# Faceball_2000_buffered_adapter_v1_0.net
KiCad netlist of a schematic drawn in Altium Designer
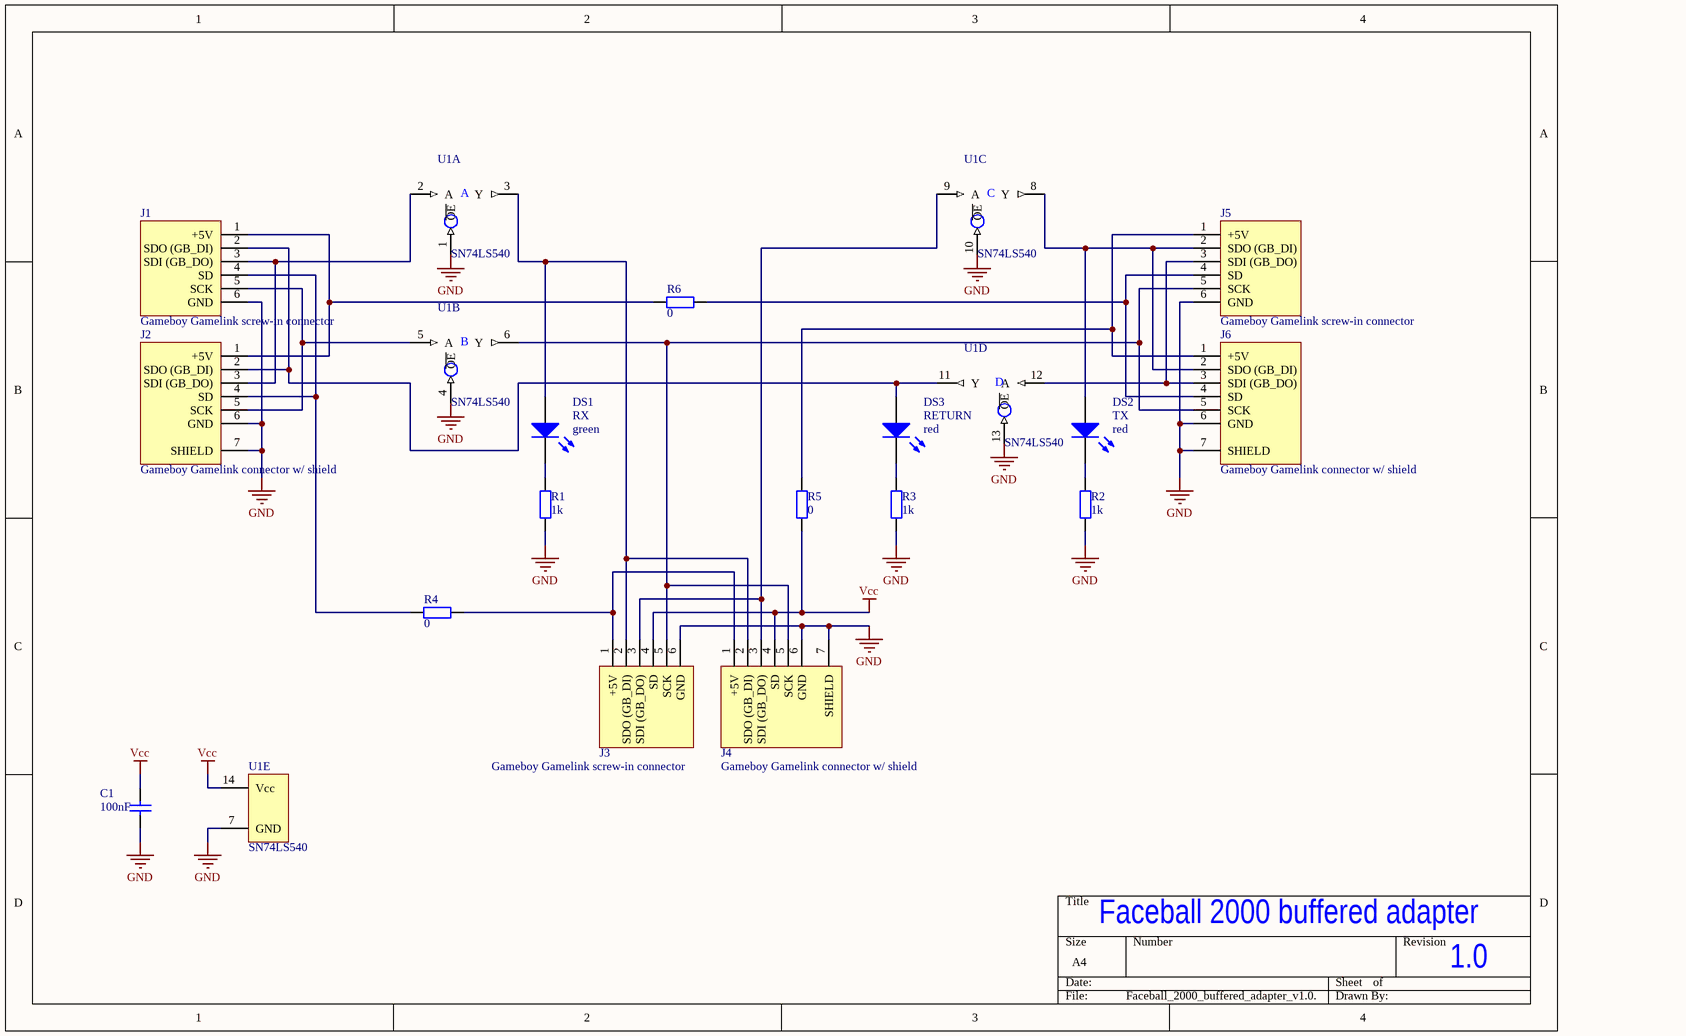
[diagram p0: Faceball_2000_buffered_adapter_v1.0.SchDoc]

(export (version "E")
  (design (tool "Eeschema 10.0.6"))
  (components
    (comp (ref "C1")
      (value "100nF")
      (footprint "CAPC1608N-0603")
      (description "Capacitor")
      (fields
        (field (name "MANUFACTURER") "Generic Components")
        (field (name "Comment") "Cap Unpol")
        (field (name "PUBLISHER") "Altium Limited")
      )
      (libsource (lib "alex_bahr") (part "Cap Unpol"))
    )
    (comp (ref "DS1")
      (value "LED")
      (footprint "CD2012-0805")
      (description "Typical LED red")
      (fields
        (field (name "MANUFACTURER") "Generic Components")
        (field (name "PURPOSE") "RX")
        (field (name "COLOR") "green")
        (field (name "PUBLISHER") "Altium Limited")
      )
      (libsource (lib "alex_bahr") (part "LED red"))
    )
    (comp (ref "DS2")
      (value "LED")
      (footprint "CD2012-0805")
      (description "Typical LED red")
      (fields
        (field (name "MANUFACTURER") "Generic Components")
        (field (name "PURPOSE") "TX")
        (field (name "COLOR") "red")
        (field (name "PUBLISHER") "Altium Limited")
      )
      (libsource (lib "alex_bahr") (part "LED red"))
    )
    (comp (ref "DS3")
      (value "LED")
      (footprint "CD2012-0805")
      (description "Typical LED red")
      (fields
        (field (name "MANUFACTURER") "Generic Components")
        (field (name "PURPOSE") "RETURN")
        (field (name "COLOR") "red")
        (field (name "PUBLISHER") "Altium Limited")
      )
      (libsource (lib "alex_bahr") (part "LED red"))
    )
    (comp (ref "J1")
      (value "Gameboy Gamelink screw-in connector")
      (footprint "Gameboy generic Gamelink connector")
      (description "Gameboy Gamelink connector")
      (libsource (lib "alex_bahr") (part "Gameboy Gamelink screw-in connector"))
    )
    (comp (ref "J2")
      (value "Gameboy Gamelink connector w/ shield")
      (footprint "Gameboy Advance Gamelink connector 2")
      (description "Gameboy Gamelink connector")
      (libsource (lib "") (part "Gameboy Gamelink connector w/ shield_1"))
    )
    (comp (ref "J3")
      (value "Gameboy Gamelink screw-in connector")
      (footprint "Gameboy generic Gamelink connector")
      (description "Gameboy Gamelink connector")
      (libsource (lib "") (part "Gameboy Gamelink screw-in connector_2"))
    )
    (comp (ref "J4")
      (value "Gameboy Gamelink connector w/ shield")
      (footprint "Gameboy Advance Gamelink connector 2")
      (description "Gameboy Gamelink connector")
      (libsource (lib "alex_bahr") (part "Gameboy Gamelink connector w/ shield"))
    )
    (comp (ref "J5")
      (value "Gameboy Gamelink screw-in connector")
      (footprint "Gameboy generic Gamelink connector")
      (description "Gameboy Gamelink connector")
      (libsource (lib "") (part "Gameboy Gamelink screw-in connector_1"))
    )
    (comp (ref "J6")
      (value "Gameboy Gamelink connector w/ shield")
      (footprint "Gameboy Advance Gamelink connector 2")
      (description "Gameboy Gamelink connector")
      (libsource (lib "") (part "Gameboy Gamelink connector w/ shield_2"))
    )
    (comp (ref "R1")
      (value "1k")
      (footprint "RESC1608N-0603")
      (description "Resistor")
      (fields (field (name "PUBLISHER") "Altium Limited"))
      (libsource (lib "") (part "Resistor_3"))
    )
    (comp (ref "R2")
      (value "1k")
      (footprint "RESC1608N-0603")
      (description "Resistor")
      (fields (field (name "PUBLISHER") "Altium Limited"))
      (libsource (lib "") (part "Resistor_3"))
    )
    (comp (ref "R3")
      (value "1k")
      (footprint "RESC1608N-0603")
      (description "Resistor")
      (fields (field (name "PUBLISHER") "Altium Limited"))
      (libsource (lib "") (part "Resistor_3"))
    )
    (comp (ref "R4")
      (value "0")
      (footprint "RESC1608N-0603")
      (description "Resistor")
      (fields (field (name "PUBLISHER") "Altium Limited"))
      (libsource (lib "") (part "Resistor_2"))
    )
    (comp (ref "R5")
      (value "0")
      (footprint "RESC1608N-0603")
      (description "Resistor")
      (fields (field (name "PUBLISHER") "Altium Limited"))
      (libsource (lib "alex_bahr") (part "Resistor"))
    )
    (comp (ref "R6")
      (value "0")
      (footprint "RESC1608N-0603")
      (description "Resistor")
      (fields (field (name "PUBLISHER") "Altium Limited"))
      (libsource (lib "") (part "Resistor_1"))
    )
    (comp (ref "U1")
      (value "SN74LS540")
      (footprint "FP-D0014A-MFG")
      (description "IC BUFFER NON-INVERT 6V 14SOIC")
      (fields
        (field (name "MANUFACTURER") "Texas Instruments")
        (field (name "MANUFACTURER PART NUMBER") "SN74LS540N")
      )
      (libsource (lib "alex_bahr") (part "SN74HC125DR"))
    )
  )
  (nets
    (net (code "1") (name "GND") (class "Default")
      (node (ref "C1") (pin "1") (pinfunction "1_1") (pintype "passive"))
      (node (ref "J1") (pin "6") (pinfunction "GND_6") (pintype "passive"))
      (node (ref "J2") (pin "6") (pinfunction "GND_6") (pintype "passive"))
      (node (ref "J2") (pin "7") (pinfunction "SHIELD_7") (pintype "passive"))
      (node (ref "J3") (pin "6") (pinfunction "GND_6") (pintype "passive"))
      (node (ref "J4") (pin "6") (pinfunction "GND_6") (pintype "passive"))
      (node (ref "J4") (pin "7") (pinfunction "SHIELD_7") (pintype "passive"))
      (node (ref "J5") (pin "6") (pinfunction "GND_6") (pintype "passive"))
      (node (ref "J6") (pin "6") (pinfunction "GND_6") (pintype "passive"))
      (node (ref "J6") (pin "7") (pinfunction "SHIELD_7") (pintype "passive"))
      (node (ref "R1") (pin "2") (pinfunction "2_2") (pintype "passive"))
      (node (ref "R2") (pin "2") (pinfunction "2_2") (pintype "passive"))
      (node (ref "R3") (pin "2") (pinfunction "2_2") (pintype "passive"))
      (node (ref "U1") (pin "1") (pinfunction "~{OE}_1") (pintype "input"))
      (node (ref "U1") (pin "10") (pinfunction "~{OE}_10") (pintype "input"))
      (node (ref "U1") (pin "13") (pinfunction "~{OE}_13") (pintype "input"))
      (node (ref "U1") (pin "4") (pinfunction "~{OE}_4") (pintype "input"))
      (node (ref "U1") (pin "7") (pinfunction "GND_7") (pintype "passive"))
    )
    (net (code "2") (name "Net-(DS1-A)") (class "Default")
      (node (ref "DS1") (pin "1") (pinfunction "A_1") (pintype "passive"))
      (node (ref "J3") (pin "2") (pinfunction "SDO_(GB_DI)_2") (pintype "passive"))
      (node (ref "J4") (pin "2") (pinfunction "SDO_(GB_DI)_2") (pintype "passive"))
      (node (ref "U1") (pin "3") (pinfunction "Y_3") (pintype "output"))
    )
    (net (code "3") (name "Net-(DS1-K)") (class "Default")
      (node (ref "DS1") (pin "2") (pinfunction "K_2") (pintype "passive"))
      (node (ref "R1") (pin "1") (pinfunction "1_1") (pintype "passive"))
    )
    (net (code "4") (name "Net-(DS2-A)") (class "Default")
      (node (ref "DS2") (pin "1") (pinfunction "A_1") (pintype "passive"))
      (node (ref "J5") (pin "2") (pinfunction "SDO_(GB_DI)_2") (pintype "passive"))
      (node (ref "J6") (pin "2") (pinfunction "SDO_(GB_DI)_2") (pintype "passive"))
      (node (ref "U1") (pin "8") (pinfunction "Y_8") (pintype "output"))
    )
    (net (code "5") (name "Net-(DS2-K)") (class "Default")
      (node (ref "DS2") (pin "2") (pinfunction "K_2") (pintype "passive"))
      (node (ref "R2") (pin "1") (pinfunction "1_1") (pintype "passive"))
    )
    (net (code "6") (name "Net-(DS3-A)") (class "Default")
      (node (ref "DS3") (pin "1") (pinfunction "A_1") (pintype "passive"))
      (node (ref "J1") (pin "2") (pinfunction "SDO_(GB_DI)_2") (pintype "passive"))
      (node (ref "J2") (pin "2") (pinfunction "SDO_(GB_DI)_2") (pintype "passive"))
      (node (ref "U1") (pin "11") (pinfunction "Y_11") (pintype "output"))
    )
    (net (code "7") (name "Net-(DS3-K)") (class "Default")
      (node (ref "DS3") (pin "2") (pinfunction "K_2") (pintype "passive"))
      (node (ref "R3") (pin "1") (pinfunction "1_1") (pintype "passive"))
    )
    (net (code "8") (name "Net-(J1-+5V)") (class "Default")
      (node (ref "J1") (pin "1") (pinfunction "+5V_1") (pintype "passive"))
      (node (ref "J2") (pin "1") (pinfunction "+5V_1") (pintype "passive"))
      (node (ref "R6") (pin "2") (pinfunction "2_2") (pintype "passive"))
    )
    (net (code "9") (name "Net-(J1-SCK)") (class "Default")
      (node (ref "J1") (pin "5") (pinfunction "SCK_5") (pintype "passive"))
      (node (ref "J2") (pin "5") (pinfunction "SCK_5") (pintype "passive"))
      (node (ref "U1") (pin "5") (pinfunction "A_5") (pintype "input"))
    )
    (net (code "10") (name "Net-(J1-SD)") (class "Default")
      (node (ref "J1") (pin "4") (pinfunction "SD_4") (pintype "passive"))
      (node (ref "J2") (pin "4") (pinfunction "SD_4") (pintype "passive"))
      (node (ref "R4") (pin "1") (pinfunction "1_1") (pintype "passive"))
    )
    (net (code "11") (name "Net-(J1-SDI_(GB_DO))") (class "Default")
      (node (ref "J1") (pin "3") (pinfunction "SDI_(GB_DO)_3") (pintype "passive"))
      (node (ref "J2") (pin "3") (pinfunction "SDI_(GB_DO)_3") (pintype "passive"))
      (node (ref "U1") (pin "2") (pinfunction "A_2") (pintype "input"))
    )
    (net (code "12") (name "Net-(J3-+5V)") (class "Default")
      (node (ref "J3") (pin "1") (pinfunction "+5V_1") (pintype "passive"))
      (node (ref "J4") (pin "1") (pinfunction "+5V_1") (pintype "passive"))
      (node (ref "R4") (pin "2") (pinfunction "2_2") (pintype "passive"))
    )
    (net (code "13") (name "Net-(J3-SCK)") (class "Default")
      (node (ref "J3") (pin "5") (pinfunction "SCK_5") (pintype "passive"))
      (node (ref "J4") (pin "5") (pinfunction "SCK_5") (pintype "passive"))
      (node (ref "J5") (pin "5") (pinfunction "SCK_5") (pintype "passive"))
      (node (ref "J6") (pin "5") (pinfunction "SCK_5") (pintype "passive"))
      (node (ref "U1") (pin "6") (pinfunction "Y_6") (pintype "output"))
    )
    (net (code "14") (name "Net-(J3-SDI_(GB_DO))") (class "Default")
      (node (ref "J3") (pin "3") (pinfunction "SDI_(GB_DO)_3") (pintype "passive"))
      (node (ref "J4") (pin "3") (pinfunction "SDI_(GB_DO)_3") (pintype "passive"))
      (node (ref "U1") (pin "9") (pinfunction "A_9") (pintype "input"))
    )
    (net (code "15") (name "Net-(J5-+5V)") (class "Default")
      (node (ref "J5") (pin "1") (pinfunction "+5V_1") (pintype "passive"))
      (node (ref "J6") (pin "1") (pinfunction "+5V_1") (pintype "passive"))
      (node (ref "R5") (pin "2") (pinfunction "2_2") (pintype "passive"))
    )
    (net (code "16") (name "Net-(J5-SD)") (class "Default")
      (node (ref "J5") (pin "4") (pinfunction "SD_4") (pintype "passive"))
      (node (ref "J6") (pin "4") (pinfunction "SD_4") (pintype "passive"))
      (node (ref "R6") (pin "1") (pinfunction "1_1") (pintype "passive"))
    )
    (net (code "17") (name "Net-(J5-SDI_(GB_DO))") (class "Default")
      (node (ref "J5") (pin "3") (pinfunction "SDI_(GB_DO)_3") (pintype "passive"))
      (node (ref "J6") (pin "3") (pinfunction "SDI_(GB_DO)_3") (pintype "passive"))
      (node (ref "U1") (pin "12") (pinfunction "A_12") (pintype "input"))
    )
    (net (code "18") (name "Vcc") (class "Default")
      (node (ref "C1") (pin "2") (pinfunction "2_2") (pintype "passive"))
      (node (ref "J3") (pin "4") (pinfunction "SD_4") (pintype "passive"))
      (node (ref "J4") (pin "4") (pinfunction "SD_4") (pintype "passive"))
      (node (ref "R5") (pin "1") (pinfunction "1_1") (pintype "passive"))
      (node (ref "U1") (pin "14") (pinfunction "Vcc_14") (pintype "passive"))
    )
  )
)
